# Sensor_Board_0x06_CO2_v2.net
KiCad netlist of a schematic drawn in EAGLE
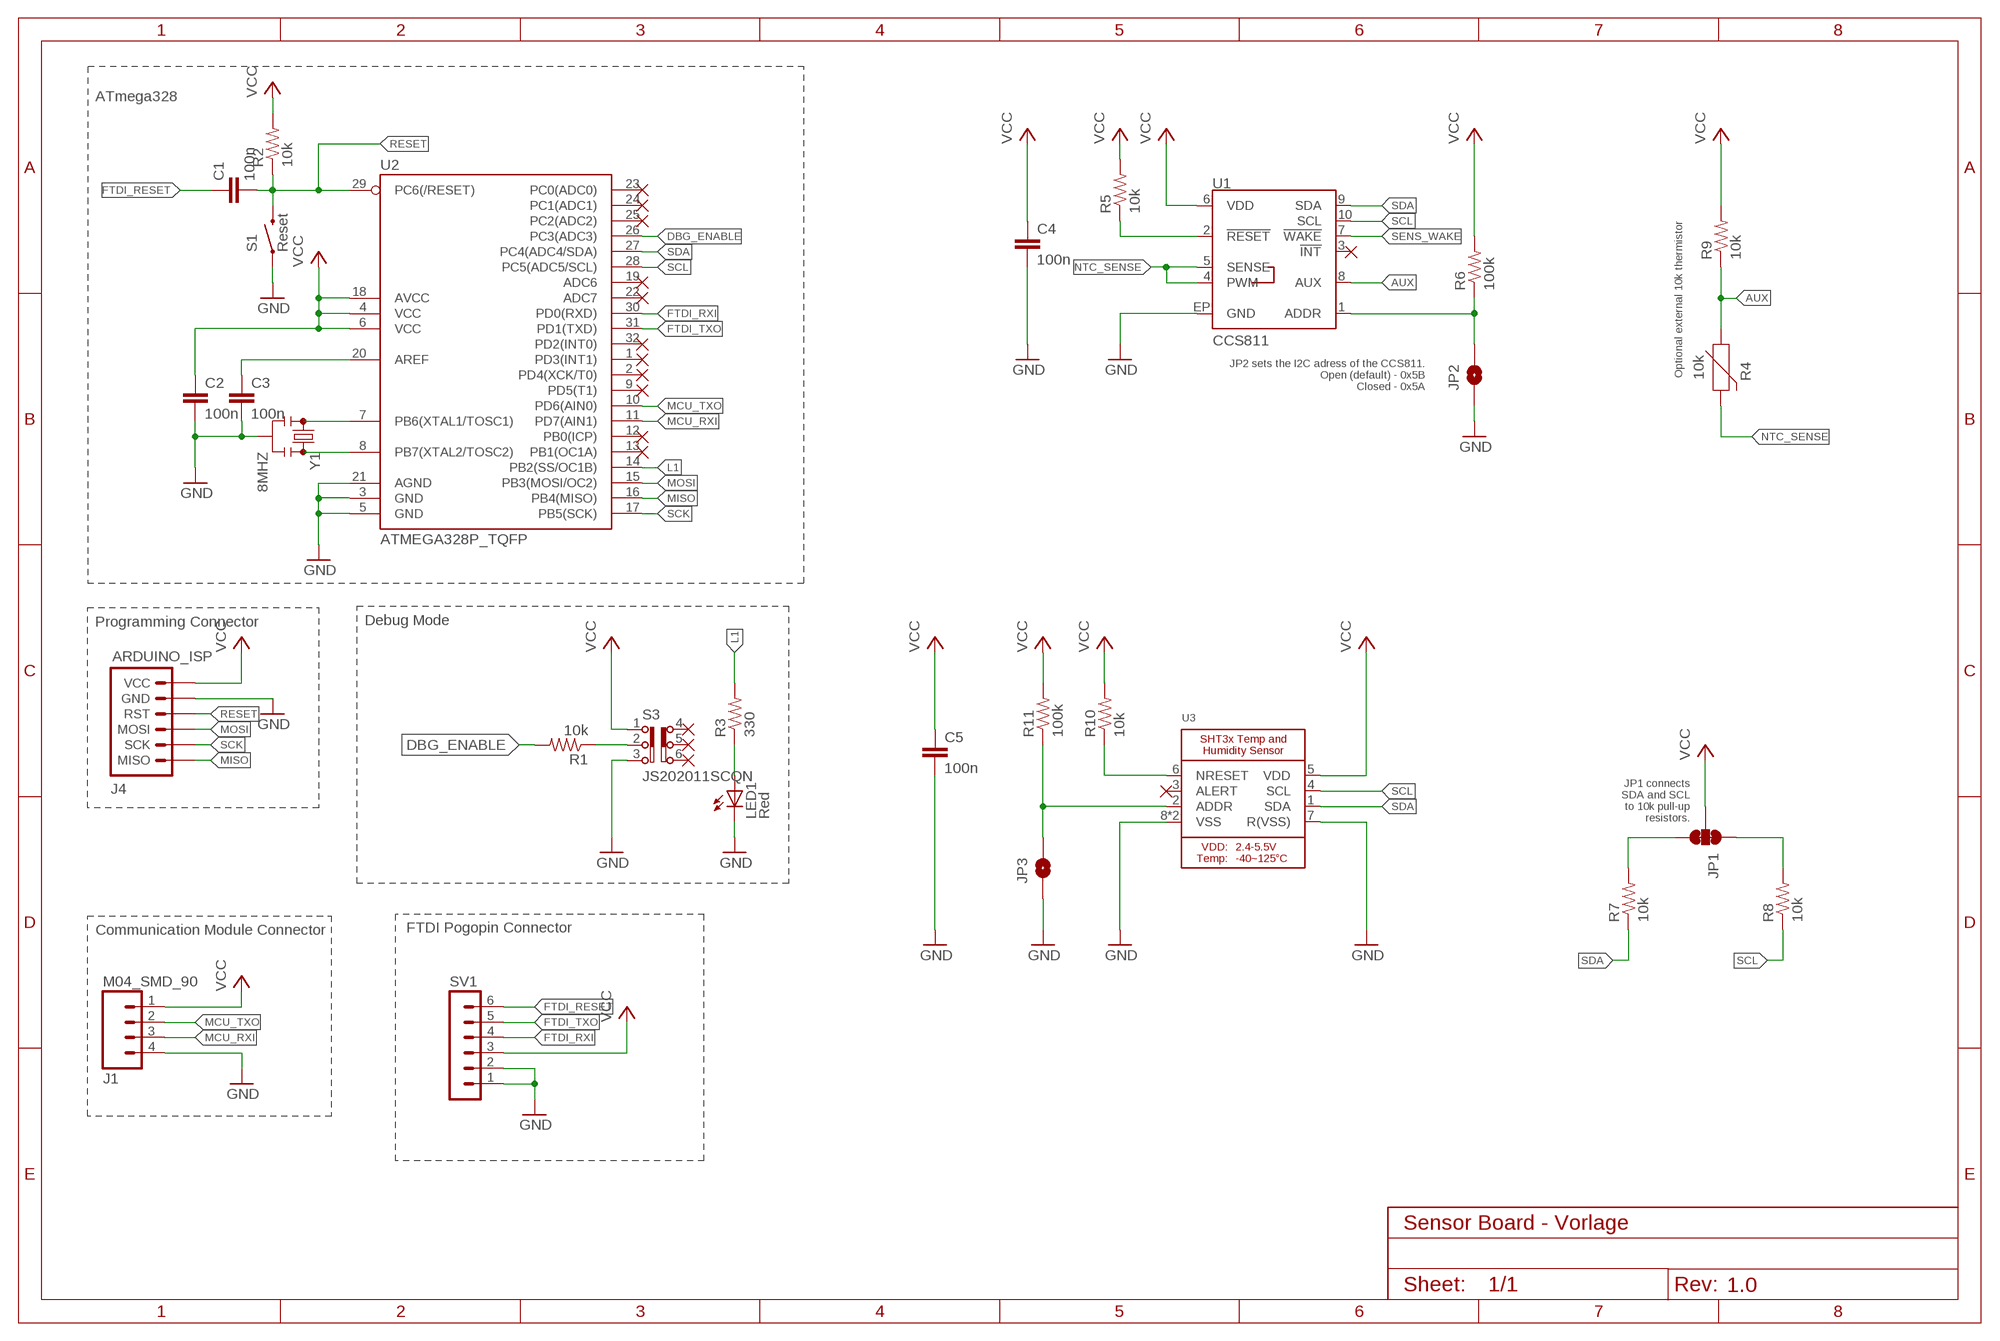
[diagram p0: schematic, sheet 1]

(export (version "E")
  (design (tool "Eeschema 10.0.6"))
  (components
    (comp (ref "C1")
      (value "100n")
      (footprint "eagle-import:C0805")
      (libsource (lib "eagle-import") (part "C"))
    )
    (comp (ref "C2")
      (value "100n")
      (footprint "eagle-import:C0805")
      (libsource (lib "eagle-import") (part "C"))
    )
    (comp (ref "C3")
      (value "100n")
      (footprint "eagle-import:C0805")
      (libsource (lib "eagle-import") (part "C"))
    )
    (comp (ref "C4")
      (value "100n")
      (footprint "eagle-import:C0805")
      (libsource (lib "eagle-import") (part "C"))
    )
    (comp (ref "C5")
      (value "100n")
      (footprint "eagle-import:C0805")
      (libsource (lib "eagle-import") (part "C"))
    )
    (comp (ref "J1")
      (value "M04_SMD_90")
      (footprint "eagle-import:M04_SMD_90")
      (libsource (lib "eagle-import") (part "M04_SMD_90"))
    )
    (comp (ref "J4")
      (value "ARDUINO_ISP")
      (footprint "eagle-import:M-2X3")
      (libsource (lib "eagle-import") (part "ARDUINO_ISP"))
    )
    (comp (ref "JP1")
      (value "SPARKFUN-JUMPERS_JUMPER-SMT_3_2-NC_TRACE_SILK")
      (footprint "eagle-import:SPARKFUN-JUMPERS_SMT-JUMPER_3_2-NC_TRACE_SILK")
      (libsource (lib "eagle-import") (part "SPARKFUN-JUMPERS_JUMPER-SMT_3_2-NC_TRACE_SILK"))
    )
    (comp (ref "JP2")
      (value "SPARKFUN-JUMPERS_JUMPER-SMT_2_NO_SILK")
      (footprint "eagle-import:SPARKFUN-JUMPERS_SMT-JUMPER_2_NO_SILK")
      (libsource (lib "eagle-import") (part "SPARKFUN-JUMPERS_JUMPER-SMT_2_NO_SILK"))
    )
    (comp (ref "JP3")
      (value "SPARKFUN-JUMPERS_JUMPER-SMT_2_NO_SILK")
      (footprint "eagle-import:SPARKFUN-JUMPERS_SMT-JUMPER_2_NO_SILK")
      (libsource (lib "eagle-import") (part "SPARKFUN-JUMPERS_JUMPER-SMT_2_NO_SILK"))
    )
    (comp (ref "LED1")
      (value "Red")
      (footprint "eagle-import:SML0805")
      (libsource (lib "eagle-import") (part "LEDSML0805"))
    )
    (comp (ref "R1")
      (value "10k")
      (footprint "eagle-import:0805")
      (libsource (lib "eagle-import") (part "RESISTOR0805-RES"))
    )
    (comp (ref "R2")
      (value "10k")
      (footprint "eagle-import:0805")
      (libsource (lib "eagle-import") (part "RESISTOR0805-RES"))
    )
    (comp (ref "R3")
      (value "330")
      (footprint "eagle-import:0805")
      (libsource (lib "eagle-import") (part "RESISTOR0805-RES"))
    )
    (comp (ref "R4")
      (value "10k")
      (footprint "eagle-import:CCS811_BREAKOUT_TEMP_0603")
      (libsource (lib "eagle-import") (part "CCS811_BREAKOUT_TEMP_NTC-THERMISTOR-0603"))
    )
    (comp (ref "R5")
      (value "10k")
      (footprint "eagle-import:0805")
      (libsource (lib "eagle-import") (part "RESISTOR0805-RES"))
    )
    (comp (ref "R6")
      (value "100k")
      (footprint "eagle-import:0805")
      (libsource (lib "eagle-import") (part "RESISTOR0805-RES"))
    )
    (comp (ref "R7")
      (value "10k")
      (footprint "eagle-import:0805")
      (libsource (lib "eagle-import") (part "RESISTOR0805-RES"))
    )
    (comp (ref "R8")
      (value "10k")
      (footprint "eagle-import:0805")
      (libsource (lib "eagle-import") (part "RESISTOR0805-RES"))
    )
    (comp (ref "R9")
      (value "10k")
      (footprint "eagle-import:0805")
      (libsource (lib "eagle-import") (part "RESISTOR0805-RES"))
    )
    (comp (ref "R10")
      (value "10k")
      (footprint "eagle-import:0805")
      (libsource (lib "eagle-import") (part "RESISTOR0805-RES"))
    )
    (comp (ref "R11")
      (value "100k")
      (footprint "eagle-import:0805")
      (libsource (lib "eagle-import") (part "RESISTOR0805-RES"))
    )
    (comp (ref "S1")
      (value "Reset")
      (footprint "eagle-import:M-PUSHBUTTON-SMD")
      (libsource (lib "eagle-import") (part "PUSHBUTTON"))
    )
    (comp (ref "S3")
      (value "JS202011SCQN")
      (footprint "eagle-import:JS202011SCQN")
      (libsource (lib "eagle-import") (part "JS202011SCQN"))
    )
    (comp (ref "SV1")
      (value "MA06-1")
      (footprint "eagle-import:MA06-1")
      (libsource (lib "eagle-import") (part "MA06-1"))
    )
    (comp (ref "U1")
      (value "CCS811")
      (footprint "eagle-import:CCS811_BREAKOUT_TEMP_LGA10")
      (libsource (lib "eagle-import") (part "CCS811_BREAKOUT_TEMP_CCS811"))
    )
    (comp (ref "U2")
      (value "ATMEGA328P_TQFP")
      (footprint "eagle-import:TQFP32-08")
      (libsource (lib "eagle-import") (part "ATMEGA328P_TQFP"))
    )
    (comp (ref "U3")
      (value "MICROBUILDER_SHT3X")
      (footprint "eagle-import:MICROBUILDER_SHT3X")
      (libsource (lib "eagle-import") (part "MICROBUILDER_SHT3X"))
    )
    (comp (ref "Y1")
      (value "8MHZ")
      (footprint "eagle-import:RESONATOR-SMD")
      (libsource (lib "eagle-import") (part "RESONATOR8MHZ"))
    )
  )
  (nets
    (net (code "1") (name "AUX") (class "Default")
      (node (ref "R4") (pin "1") (pinfunction "1_1") (pintype "bidirectional"))
      (node (ref "R9") (pin "1") (pinfunction "1_1") (pintype "passive"))
      (node (ref "U1") (pin "8") (pinfunction "AUX_8") (pintype "bidirectional"))
    )
    (net (code "2") (name "DBG_ENABLE") (class "Default")
      (node (ref "R1") (pin "2") (pinfunction "2_2") (pintype "passive"))
      (node (ref "U2") (pin "26") (pinfunction "PC3(ADC3)_26") (pintype "bidirectional"))
    )
    (net (code "3") (name "FTDI_RESET") (class "Default")
      (node (ref "C1") (pin "1") (pinfunction "1_1") (pintype "passive"))
      (node (ref "SV1") (pin "6") (pinfunction "6_6") (pintype "passive"))
    )
    (net (code "4") (name "FTDI_RXI") (class "Default")
      (node (ref "SV1") (pin "4") (pinfunction "4_4") (pintype "passive"))
      (node (ref "U2") (pin "30") (pinfunction "PD0(RXD)_30") (pintype "bidirectional"))
    )
    (net (code "5") (name "FTDI_TXO") (class "Default")
      (node (ref "SV1") (pin "5") (pinfunction "5_5") (pintype "passive"))
      (node (ref "U2") (pin "31") (pinfunction "PD1(TXD)_31") (pintype "bidirectional"))
    )
    (net (code "6") (name "GND") (class "Default")
      (node (ref "C2") (pin "2") (pinfunction "2_2") (pintype "passive"))
      (node (ref "C3") (pin "2") (pinfunction "2_2") (pintype "passive"))
      (node (ref "C4") (pin "2") (pinfunction "2_2") (pintype "passive"))
      (node (ref "C5") (pin "2") (pinfunction "2_2") (pintype "passive"))
      (node (ref "J1") (pin "4") (pinfunction "4_4") (pintype "passive"))
      (node (ref "J4") (pin "P$5") (pinfunction "GND_P$5") (pintype "passive"))
      (node (ref "JP2") (pin "1") (pinfunction "1_1") (pintype "passive"))
      (node (ref "JP3") (pin "1") (pinfunction "1_1") (pintype "passive"))
      (node (ref "LED1") (pin "C") (pinfunction "C_C") (pintype "passive"))
      (node (ref "S1") (pin "1") (pinfunction "LEFT_1") (pintype "passive"))
      (node (ref "S1") (pin "2") (pinfunction "LEFT_2") (pintype "passive"))
      (node (ref "S3") (pin "3") (pinfunction "3_3") (pintype "passive"))
      (node (ref "SV1") (pin "1") (pinfunction "1_1") (pintype "passive"))
      (node (ref "SV1") (pin "2") (pinfunction "2_2") (pintype "passive"))
      (node (ref "U1") (pin "EP") (pinfunction "GND_EP") (pintype "bidirectional"))
      (node (ref "U2") (pin "21") (pinfunction "AGND_21") (pintype "bidirectional"))
      (node (ref "U2") (pin "3") (pinfunction "GND_3") (pintype "bidirectional"))
      (node (ref "U2") (pin "5") (pinfunction "GND_5") (pintype "bidirectional"))
      (node (ref "U3") (pin "7") (pinfunction "R(VSS)_7") (pintype "bidirectional"))
      (node (ref "U3") (pin "8") (pinfunction "VSS_8") (pintype "power_in"))
      (node (ref "U3") (pin "THERMAL") (pinfunction "VSS_THERMAL") (pintype "power_in"))
      (node (ref "Y1") (pin "2") (pinfunction "2_2") (pintype "passive"))
    )
    (net (code "7") (name "L1") (class "Default")
      (node (ref "R3") (pin "2") (pinfunction "2_2") (pintype "passive"))
      (node (ref "U2") (pin "14") (pinfunction "PB2(SS/OC1B)_14") (pintype "bidirectional"))
    )
    (net (code "8") (name "MCU_RXI") (class "Default")
      (node (ref "J1") (pin "3") (pinfunction "3_3") (pintype "passive"))
      (node (ref "U2") (pin "11") (pinfunction "PD7(AIN1)_11") (pintype "bidirectional"))
    )
    (net (code "9") (name "MCU_TXO") (class "Default")
      (node (ref "J1") (pin "2") (pinfunction "2_2") (pintype "passive"))
      (node (ref "U2") (pin "10") (pinfunction "PD6(AIN0)_10") (pintype "bidirectional"))
    )
    (net (code "10") (name "MISO") (class "Default")
      (node (ref "J4") (pin "P$1") (pinfunction "MISO_P$1") (pintype "passive"))
      (node (ref "U2") (pin "16") (pinfunction "PB4(MISO)_16") (pintype "bidirectional"))
    )
    (net (code "11") (name "MOSI") (class "Default")
      (node (ref "J4") (pin "P$3") (pinfunction "MOSI_P$3") (pintype "passive"))
      (node (ref "U2") (pin "15") (pinfunction "PB3(MOSI/OC2)_15") (pintype "bidirectional"))
    )
    (net (code "12") (name "NTC_SENSE") (class "Default")
      (node (ref "R4") (pin "2") (pinfunction "2_2") (pintype "bidirectional"))
      (node (ref "U1") (pin "4") (pinfunction "PWM_4") (pintype "bidirectional"))
      (node (ref "U1") (pin "5") (pinfunction "SENSE_5") (pintype "bidirectional"))
    )
    (net (code "13") (name "Net-(JP1-Pad1)") (class "Default")
      (node (ref "JP1") (pin "1") (pinfunction "1_1") (pintype "passive"))
      (node (ref "R8") (pin "2") (pinfunction "2_2") (pintype "passive"))
    )
    (net (code "14") (name "Net-(JP1-Pad3)") (class "Default")
      (node (ref "JP1") (pin "3") (pinfunction "3_3") (pintype "passive"))
      (node (ref "R7") (pin "2") (pinfunction "2_2") (pintype "passive"))
    )
    (net (code "15") (name "Net-(LED1-PadA)") (class "Default")
      (node (ref "LED1") (pin "A") (pinfunction "A_A") (pintype "passive"))
      (node (ref "R3") (pin "1") (pinfunction "1_1") (pintype "passive"))
    )
    (net (code "16") (name "Net-(R1-Pad1)") (class "Default")
      (node (ref "R1") (pin "1") (pinfunction "1_1") (pintype "passive"))
      (node (ref "S3") (pin "2") (pinfunction "2_2") (pintype "passive"))
    )
    (net (code "17") (name "Net-(U1-ADDR)") (class "Default")
      (node (ref "JP2") (pin "2") (pinfunction "2_2") (pintype "passive"))
      (node (ref "R6") (pin "1") (pinfunction "1_1") (pintype "passive"))
      (node (ref "U1") (pin "1") (pinfunction "ADDR_1") (pintype "bidirectional"))
    )
    (net (code "18") (name "Net-(U1-~{RESET})") (class "Default")
      (node (ref "R5") (pin "1") (pinfunction "1_1") (pintype "passive"))
      (node (ref "U1") (pin "2") (pinfunction "~{RESET}_2") (pintype "bidirectional"))
    )
    (net (code "19") (name "Net-(U2-AREF)") (class "Default")
      (node (ref "C3") (pin "1") (pinfunction "1_1") (pintype "passive"))
      (node (ref "U2") (pin "20") (pinfunction "AREF_20") (pintype "bidirectional"))
    )
    (net (code "20") (name "Net-(U2-PB6(XTAL1{slash}TOSC1))") (class "Default")
      (node (ref "U2") (pin "7") (pinfunction "PB6(XTAL1/TOSC1)_7") (pintype "bidirectional"))
      (node (ref "Y1") (pin "1") (pinfunction "1_1") (pintype "passive"))
    )
    (net (code "21") (name "Net-(U2-PB7(XTAL2{slash}TOSC2))") (class "Default")
      (node (ref "U2") (pin "8") (pinfunction "PB7(XTAL2/TOSC2)_8") (pintype "bidirectional"))
      (node (ref "Y1") (pin "3") (pinfunction "3_3") (pintype "passive"))
    )
    (net (code "22") (name "Net-(U3-ADDR)") (class "Default")
      (node (ref "JP3") (pin "2") (pinfunction "2_2") (pintype "passive"))
      (node (ref "R11") (pin "1") (pinfunction "1_1") (pintype "passive"))
      (node (ref "U3") (pin "2") (pinfunction "ADDR_2") (pintype "bidirectional"))
    )
    (net (code "23") (name "Net-(U3-NRESET)") (class "Default")
      (node (ref "R10") (pin "1") (pinfunction "1_1") (pintype "passive"))
      (node (ref "U3") (pin "6") (pinfunction "NRESET_6") (pintype "bidirectional"))
    )
    (net (code "24") (name "RESET") (class "Default")
      (node (ref "C1") (pin "2") (pinfunction "2_2") (pintype "passive"))
      (node (ref "J4") (pin "P$4") (pinfunction "RST_P$4") (pintype "passive"))
      (node (ref "R2") (pin "1") (pinfunction "1_1") (pintype "passive"))
      (node (ref "S1") (pin "3") (pinfunction "RIGHT_3") (pintype "passive"))
      (node (ref "S1") (pin "4") (pinfunction "RIGHT_4") (pintype "passive"))
      (node (ref "U2") (pin "29") (pinfunction "PC6(/RESET)_29") (pintype "bidirectional"))
    )
    (net (code "25") (name "SCK") (class "Default")
      (node (ref "J4") (pin "P$2") (pinfunction "SCK_P$2") (pintype "passive"))
      (node (ref "U2") (pin "17") (pinfunction "PB5(SCK)_17") (pintype "bidirectional"))
    )
    (net (code "26") (name "SCL") (class "Default")
      (node (ref "R8") (pin "1") (pinfunction "1_1") (pintype "passive"))
      (node (ref "U1") (pin "10") (pinfunction "SCL_10") (pintype "bidirectional"))
      (node (ref "U2") (pin "28") (pinfunction "PC5(ADC5/SCL)_28") (pintype "bidirectional"))
      (node (ref "U3") (pin "4") (pinfunction "SCL_4") (pintype "bidirectional"))
    )
    (net (code "27") (name "SDA") (class "Default")
      (node (ref "R7") (pin "1") (pinfunction "1_1") (pintype "passive"))
      (node (ref "U1") (pin "9") (pinfunction "SDA_9") (pintype "bidirectional"))
      (node (ref "U2") (pin "27") (pinfunction "PC4(ADC4/SDA)_27") (pintype "bidirectional"))
      (node (ref "U3") (pin "1") (pinfunction "SDA_1") (pintype "bidirectional"))
    )
    (net (code "28") (name "SENS_WAKE") (class "Default")
      (node (ref "U1") (pin "7") (pinfunction "~{WAKE}_7") (pintype "bidirectional"))
    )
    (net (code "29") (name "VCC") (class "Default")
      (node (ref "C2") (pin "1") (pinfunction "1_1") (pintype "passive"))
      (node (ref "C4") (pin "1") (pinfunction "1_1") (pintype "passive"))
      (node (ref "C5") (pin "1") (pinfunction "1_1") (pintype "passive"))
      (node (ref "J1") (pin "1") (pinfunction "1_1") (pintype "passive"))
      (node (ref "J4") (pin "P$6") (pinfunction "VCC_P$6") (pintype "passive"))
      (node (ref "JP1") (pin "2") (pinfunction "2_2") (pintype "passive"))
      (node (ref "R10") (pin "2") (pinfunction "2_2") (pintype "passive"))
      (node (ref "R11") (pin "2") (pinfunction "2_2") (pintype "passive"))
      (node (ref "R2") (pin "2") (pinfunction "2_2") (pintype "passive"))
      (node (ref "R5") (pin "2") (pinfunction "2_2") (pintype "passive"))
      (node (ref "R6") (pin "2") (pinfunction "2_2") (pintype "passive"))
      (node (ref "R9") (pin "2") (pinfunction "2_2") (pintype "passive"))
      (node (ref "S3") (pin "1") (pinfunction "1_1") (pintype "passive"))
      (node (ref "SV1") (pin "3") (pinfunction "3_3") (pintype "passive"))
      (node (ref "U1") (pin "6") (pinfunction "VDD_6") (pintype "bidirectional"))
      (node (ref "U2") (pin "18") (pinfunction "AVCC_18") (pintype "bidirectional"))
      (node (ref "U2") (pin "4") (pinfunction "VCC_4") (pintype "bidirectional"))
      (node (ref "U2") (pin "6") (pinfunction "VCC_6") (pintype "bidirectional"))
      (node (ref "U3") (pin "5") (pinfunction "VDD_5") (pintype "power_in"))
    )
    (net (code "30") (name "unconnected-(S3-Pad4)") (class "Default")
      (node (ref "S3") (pin "4") (pinfunction "4_4") (pintype "passive"))
    )
    (net (code "31") (name "unconnected-(S3-Pad5)") (class "Default")
      (node (ref "S3") (pin "5") (pinfunction "5_5") (pintype "passive"))
    )
    (net (code "32") (name "unconnected-(S3-Pad6)") (class "Default")
      (node (ref "S3") (pin "6") (pinfunction "6_6") (pintype "passive"))
    )
    (net (code "33") (name "unconnected-(U1-~{INT}-Pad3)") (class "Default")
      (node (ref "U1") (pin "3") (pinfunction "~{INT}_3") (pintype "bidirectional"))
    )
    (net (code "34") (name "unconnected-(U2-ADC6-Pad19)") (class "Default")
      (node (ref "U2") (pin "19") (pinfunction "ADC6_19") (pintype "bidirectional"))
    )
    (net (code "35") (name "unconnected-(U2-ADC7-Pad22)") (class "Default")
      (node (ref "U2") (pin "22") (pinfunction "ADC7_22") (pintype "bidirectional"))
    )
    (net (code "36") (name "unconnected-(U2-PB0(ICP)-Pad12)") (class "Default")
      (node (ref "U2") (pin "12") (pinfunction "PB0(ICP)_12") (pintype "bidirectional"))
    )
    (net (code "37") (name "unconnected-(U2-PB1(OC1A)-Pad13)") (class "Default")
      (node (ref "U2") (pin "13") (pinfunction "PB1(OC1A)_13") (pintype "bidirectional"))
    )
    (net (code "38") (name "unconnected-(U2-PC0(ADC0)-Pad23)") (class "Default")
      (node (ref "U2") (pin "23") (pinfunction "PC0(ADC0)_23") (pintype "bidirectional"))
    )
    (net (code "39") (name "unconnected-(U2-PC1(ADC1)-Pad24)") (class "Default")
      (node (ref "U2") (pin "24") (pinfunction "PC1(ADC1)_24") (pintype "bidirectional"))
    )
    (net (code "40") (name "unconnected-(U2-PC2(ADC2)-Pad25)") (class "Default")
      (node (ref "U2") (pin "25") (pinfunction "PC2(ADC2)_25") (pintype "bidirectional"))
    )
    (net (code "41") (name "unconnected-(U2-PD2(INT0)-Pad32)") (class "Default")
      (node (ref "U2") (pin "32") (pinfunction "PD2(INT0)_32") (pintype "bidirectional"))
    )
    (net (code "42") (name "unconnected-(U2-PD3(INT1)-Pad1)") (class "Default")
      (node (ref "U2") (pin "1") (pinfunction "PD3(INT1)_1") (pintype "bidirectional"))
    )
    (net (code "43") (name "unconnected-(U2-PD4(XCK{slash}T0)-Pad2)") (class "Default")
      (node (ref "U2") (pin "2") (pinfunction "PD4(XCK/T0)_2") (pintype "bidirectional"))
    )
    (net (code "44") (name "unconnected-(U2-PD5(T1)-Pad9)") (class "Default")
      (node (ref "U2") (pin "9") (pinfunction "PD5(T1)_9") (pintype "bidirectional"))
    )
    (net (code "45") (name "unconnected-(U3-ALERT-Pad3)") (class "Default")
      (node (ref "U3") (pin "3") (pinfunction "ALERT_3") (pintype "bidirectional"))
    )
  )
)
